# tvbgone3.net
KiCad netlist of a schematic drawn in EAGLE
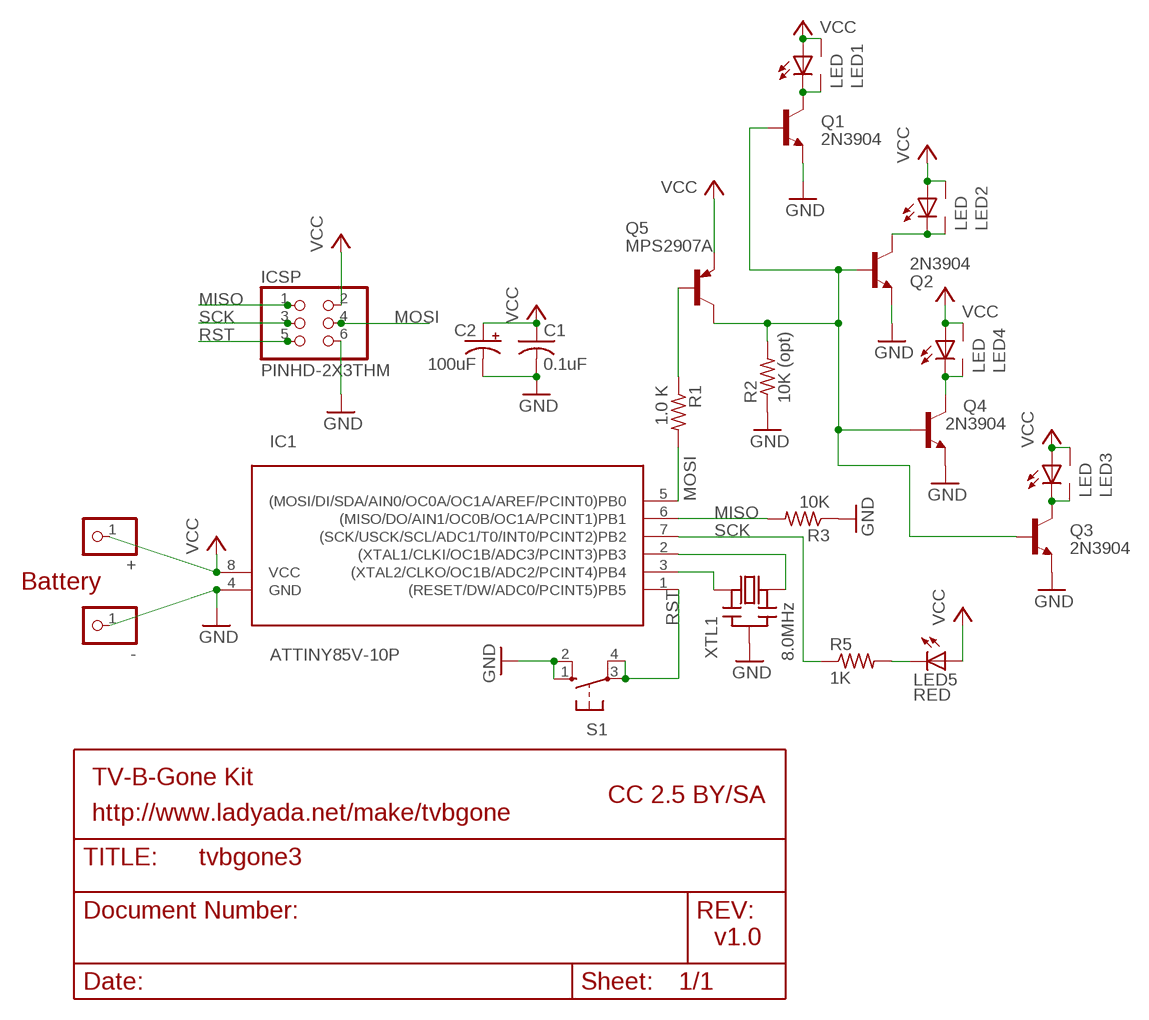
[diagram p0: schematic, sheet 1]

(export (version "E")
  (design (tool "Eeschema 10.0.6"))
  (components
    (comp (ref "+")
      (value "PINHD-1X1")
      (footprint "eagle-import:1X01")
      (libsource (lib "eagle-import") (part "PINHD-1X1"))
    )
    (comp (ref "-")
      (value "PINHD-1X1")
      (footprint "eagle-import:1X01")
      (libsource (lib "eagle-import") (part "PINHD-1X1"))
    )
    (comp (ref "C1")
      (value "0.1uF")
      (footprint "eagle-import:C025-025X050")
      (libsource (lib "eagle-import") (part "C-US025-025X050"))
    )
    (comp (ref "C2")
      (value "100uF")
      (footprint "eagle-import:E2,5-5")
      (libsource (lib "eagle-import") (part "CPOL-USE2.5-5"))
    )
    (comp (ref "IC1")
      (value "ATTINY85V-10P")
      (footprint "eagle-import:DIL08")
      (libsource (lib "eagle-import") (part "ATTINY85PV-10"))
    )
    (comp (ref "ICSP")
      (value "PINHD-2X3THM")
      (footprint "eagle-import:ISP6")
      (libsource (lib "eagle-import") (part "PINHD-2X3THM"))
    )
    (comp (ref "LED1")
      (value "LED")
      (footprint "eagle-import:5MM-SIDE")
      (libsource (lib "eagle-import") (part "tvbgone_LED"))
    )
    (comp (ref "LED2")
      (value "LED")
      (footprint "eagle-import:5MM-SIDE")
      (libsource (lib "eagle-import") (part "tvbgone_LED"))
    )
    (comp (ref "LED3")
      (value "LED")
      (footprint "eagle-import:5MM-SIDE")
      (libsource (lib "eagle-import") (part "tvbgone_LED"))
    )
    (comp (ref "LED4")
      (value "LED")
      (footprint "eagle-import:5MM-SIDE")
      (libsource (lib "eagle-import") (part "tvbgone_LED"))
    )
    (comp (ref "LED5")
      (value "RED")
      (footprint "eagle-import:LED3MM")
      (libsource (lib "eagle-import") (part "LED3MM"))
    )
    (comp (ref "Q1")
      (value "2N3904")
      (footprint "eagle-import:TO92-EZ")
      (libsource (lib "eagle-import") (part "2N3904EZ"))
    )
    (comp (ref "Q2")
      (value "2N3904")
      (footprint "eagle-import:TO92-EZ")
      (libsource (lib "eagle-import") (part "2N3904EZ"))
    )
    (comp (ref "Q3")
      (value "2N3904")
      (footprint "eagle-import:TO92-EZ")
      (libsource (lib "eagle-import") (part "2N3904EZ"))
    )
    (comp (ref "Q4")
      (value "2N3904")
      (footprint "eagle-import:TO92-EZ")
      (libsource (lib "eagle-import") (part "2N3904EZ"))
    )
    (comp (ref "Q5")
      (value "MPS2907A")
      (footprint "eagle-import:TO92-CBE")
      (libsource (lib "eagle-import") (part "MPS2907A"))
    )
    (comp (ref "R1")
      (value "1.0 K")
      (footprint "eagle-import:0207_10")
      (libsource (lib "eagle-import") (part "R-US_0207/10"))
    )
    (comp (ref "R2")
      (value "10K (opt)")
      (footprint "eagle-import:0207_10")
      (libsource (lib "eagle-import") (part "R-US_0207/10"))
    )
    (comp (ref "R3")
      (value "10K")
      (footprint "eagle-import:0207_10")
      (libsource (lib "eagle-import") (part "R-US_0207/10"))
    )
    (comp (ref "R5")
      (value "1K")
      (footprint "eagle-import:0207_10")
      (libsource (lib "eagle-import") (part "R-US_0207/10"))
    )
    (comp (ref "S1")
      (value "10-XX")
      (footprint "eagle-import:B3F-10XX")
      (libsource (lib "eagle-import") (part "10-XX"))
    )
    (comp (ref "XTL1")
      (value "8.0MHz")
      (footprint "eagle-import:CERM_OSC")
      (libsource (lib "eagle-import") (part "CERMOSCILL"))
    )
  )
  (nets
    (net (code "1") (name "/MISO") (class "Default")
      (node (ref "IC1") (pin "6") (pinfunction "(MISO/DO/AIN1/OC0B/OC1A/PCINT1)PB1_6") (pintype "bidirectional"))
      (node (ref "ICSP") (pin "1") (pinfunction "1_1") (pintype "passive"))
      (node (ref "R3") (pin "2") (pinfunction "2_2") (pintype "passive"))
    )
    (net (code "2") (name "/MOSI") (class "Default")
      (node (ref "IC1") (pin "5") (pinfunction "(MOSI/DI/SDA/AIN0/OC0A/OC1A/AREF/PCINT0)PB0_5") (pintype "bidirectional"))
      (node (ref "ICSP") (pin "4") (pinfunction "4_4") (pintype "passive"))
      (node (ref "R1") (pin "2") (pinfunction "2_2") (pintype "passive"))
    )
    (net (code "3") (name "/RST") (class "Default")
      (node (ref "IC1") (pin "1") (pinfunction "(RESET/DW/ADC0/PCINT5)PB5_1") (pintype "bidirectional"))
      (node (ref "ICSP") (pin "5") (pinfunction "5_5") (pintype "passive"))
      (node (ref "S1") (pin "3") (pinfunction "P_3") (pintype "passive"))
      (node (ref "S1") (pin "4") (pinfunction "P1_4") (pintype "passive"))
    )
    (net (code "4") (name "/SCK") (class "Default")
      (node (ref "IC1") (pin "7") (pinfunction "(SCK/USCK/SCL/ADC1/T0/INT0/PCINT2)PB2_7") (pintype "bidirectional"))
      (node (ref "ICSP") (pin "3") (pinfunction "3_3") (pintype "passive"))
      (node (ref "R5") (pin "1") (pinfunction "1_1") (pintype "passive"))
    )
    (net (code "5") (name "GND") (class "Default")
      (node (ref "-") (pin "1") (pinfunction "1_1") (pintype "passive"))
      (node (ref "C1") (pin "2") (pinfunction "2_2") (pintype "passive"))
      (node (ref "C2") (pin "-") (pinfunction "-_-") (pintype "passive"))
      (node (ref "IC1") (pin "4") (pinfunction "GND_4") (pintype "bidirectional"))
      (node (ref "ICSP") (pin "6") (pinfunction "6_6") (pintype "passive"))
      (node (ref "Q1") (pin "3") (pinfunction "E_3") (pintype "passive"))
      (node (ref "Q2") (pin "3") (pinfunction "E_3") (pintype "passive"))
      (node (ref "Q3") (pin "3") (pinfunction "E_3") (pintype "passive"))
      (node (ref "Q4") (pin "3") (pinfunction "E_3") (pintype "passive"))
      (node (ref "R2") (pin "1") (pinfunction "1_1") (pintype "passive"))
      (node (ref "R3") (pin "1") (pinfunction "1_1") (pintype "passive"))
      (node (ref "S1") (pin "1") (pinfunction "S_1") (pintype "passive"))
      (node (ref "S1") (pin "2") (pinfunction "S1_2") (pintype "passive"))
      (node (ref "XTL1") (pin "P$2") (pinfunction "GND_P$2") (pintype "bidirectional"))
    )
    (net (code "6") (name "Net-(IC1-(XTAL1{slash}CLKI{slash}OC1B{slash}ADC3{slash}PCINT3)PB3)") (class "Default")
      (node (ref "IC1") (pin "2") (pinfunction "(XTAL1/CLKI/OC1B/ADC3/PCINT3)PB3_2") (pintype "bidirectional"))
      (node (ref "XTL1") (pin "P$3") (pinfunction "OUT_P$3") (pintype "bidirectional"))
    )
    (net (code "7") (name "Net-(IC1-(XTAL2{slash}CLKO{slash}OC1B{slash}ADC2{slash}PCINT4)PB4)") (class "Default")
      (node (ref "IC1") (pin "3") (pinfunction "(XTAL2/CLKO/OC1B/ADC2/PCINT4)PB4_3") (pintype "bidirectional"))
      (node (ref "XTL1") (pin "P$1") (pinfunction "IN_P$1") (pintype "bidirectional"))
    )
    (net (code "8") (name "Net-(LED1-C)") (class "Default")
      (node (ref "LED1") (pin "K") (pinfunction "C_K") (pintype "passive"))
      (node (ref "LED1") (pin "K2") (pinfunction "C1_K2") (pintype "passive"))
      (node (ref "Q1") (pin "1") (pinfunction "C_1") (pintype "passive"))
    )
    (net (code "9") (name "Net-(LED2-C)") (class "Default")
      (node (ref "LED2") (pin "K") (pinfunction "C_K") (pintype "passive"))
      (node (ref "LED2") (pin "K2") (pinfunction "C1_K2") (pintype "passive"))
      (node (ref "Q2") (pin "1") (pinfunction "C_1") (pintype "passive"))
    )
    (net (code "10") (name "Net-(LED3-C)") (class "Default")
      (node (ref "LED3") (pin "K") (pinfunction "C_K") (pintype "passive"))
      (node (ref "LED3") (pin "K2") (pinfunction "C1_K2") (pintype "passive"))
      (node (ref "Q3") (pin "1") (pinfunction "C_1") (pintype "passive"))
    )
    (net (code "11") (name "Net-(LED4-C)") (class "Default")
      (node (ref "LED4") (pin "K") (pinfunction "C_K") (pintype "passive"))
      (node (ref "LED4") (pin "K2") (pinfunction "C1_K2") (pintype "passive"))
      (node (ref "Q4") (pin "1") (pinfunction "C_1") (pintype "passive"))
    )
    (net (code "12") (name "Net-(LED5-C)") (class "Default")
      (node (ref "LED5") (pin "K") (pinfunction "C_K") (pintype "passive"))
      (node (ref "R5") (pin "2") (pinfunction "2_2") (pintype "passive"))
    )
    (net (code "13") (name "Net-(Q1-B)") (class "Default")
      (node (ref "Q1") (pin "2") (pinfunction "B_2") (pintype "passive"))
      (node (ref "Q2") (pin "2") (pinfunction "B_2") (pintype "passive"))
      (node (ref "Q3") (pin "2") (pinfunction "B_2") (pintype "passive"))
      (node (ref "Q4") (pin "2") (pinfunction "B_2") (pintype "passive"))
      (node (ref "Q5") (pin "C") (pinfunction "C_C") (pintype "passive"))
      (node (ref "R2") (pin "2") (pinfunction "2_2") (pintype "passive"))
    )
    (net (code "14") (name "Net-(Q5-PadB)") (class "Default")
      (node (ref "Q5") (pin "B") (pinfunction "B_B") (pintype "passive"))
      (node (ref "R1") (pin "1") (pinfunction "1_1") (pintype "passive"))
    )
    (net (code "15") (name "VCC") (class "Default")
      (node (ref "+") (pin "1") (pinfunction "1_1") (pintype "passive"))
      (node (ref "C1") (pin "1") (pinfunction "1_1") (pintype "passive"))
      (node (ref "C2") (pin "+") (pinfunction "+_+") (pintype "passive"))
      (node (ref "IC1") (pin "8") (pinfunction "VCC_8") (pintype "bidirectional"))
      (node (ref "ICSP") (pin "2") (pinfunction "2_2") (pintype "passive"))
      (node (ref "LED1") (pin "A") (pinfunction "A_A") (pintype "passive"))
      (node (ref "LED1") (pin "A2") (pinfunction "A1_A2") (pintype "passive"))
      (node (ref "LED2") (pin "A") (pinfunction "A_A") (pintype "passive"))
      (node (ref "LED2") (pin "A2") (pinfunction "A1_A2") (pintype "passive"))
      (node (ref "LED3") (pin "A") (pinfunction "A_A") (pintype "passive"))
      (node (ref "LED3") (pin "A2") (pinfunction "A1_A2") (pintype "passive"))
      (node (ref "LED4") (pin "A") (pinfunction "A_A") (pintype "passive"))
      (node (ref "LED4") (pin "A2") (pinfunction "A1_A2") (pintype "passive"))
      (node (ref "LED5") (pin "A") (pinfunction "A_A") (pintype "passive"))
      (node (ref "Q5") (pin "E") (pinfunction "E_E") (pintype "passive"))
    )
  )
)
